# ScanBook.net
KiCad netlist of a schematic drawn in EAGLE
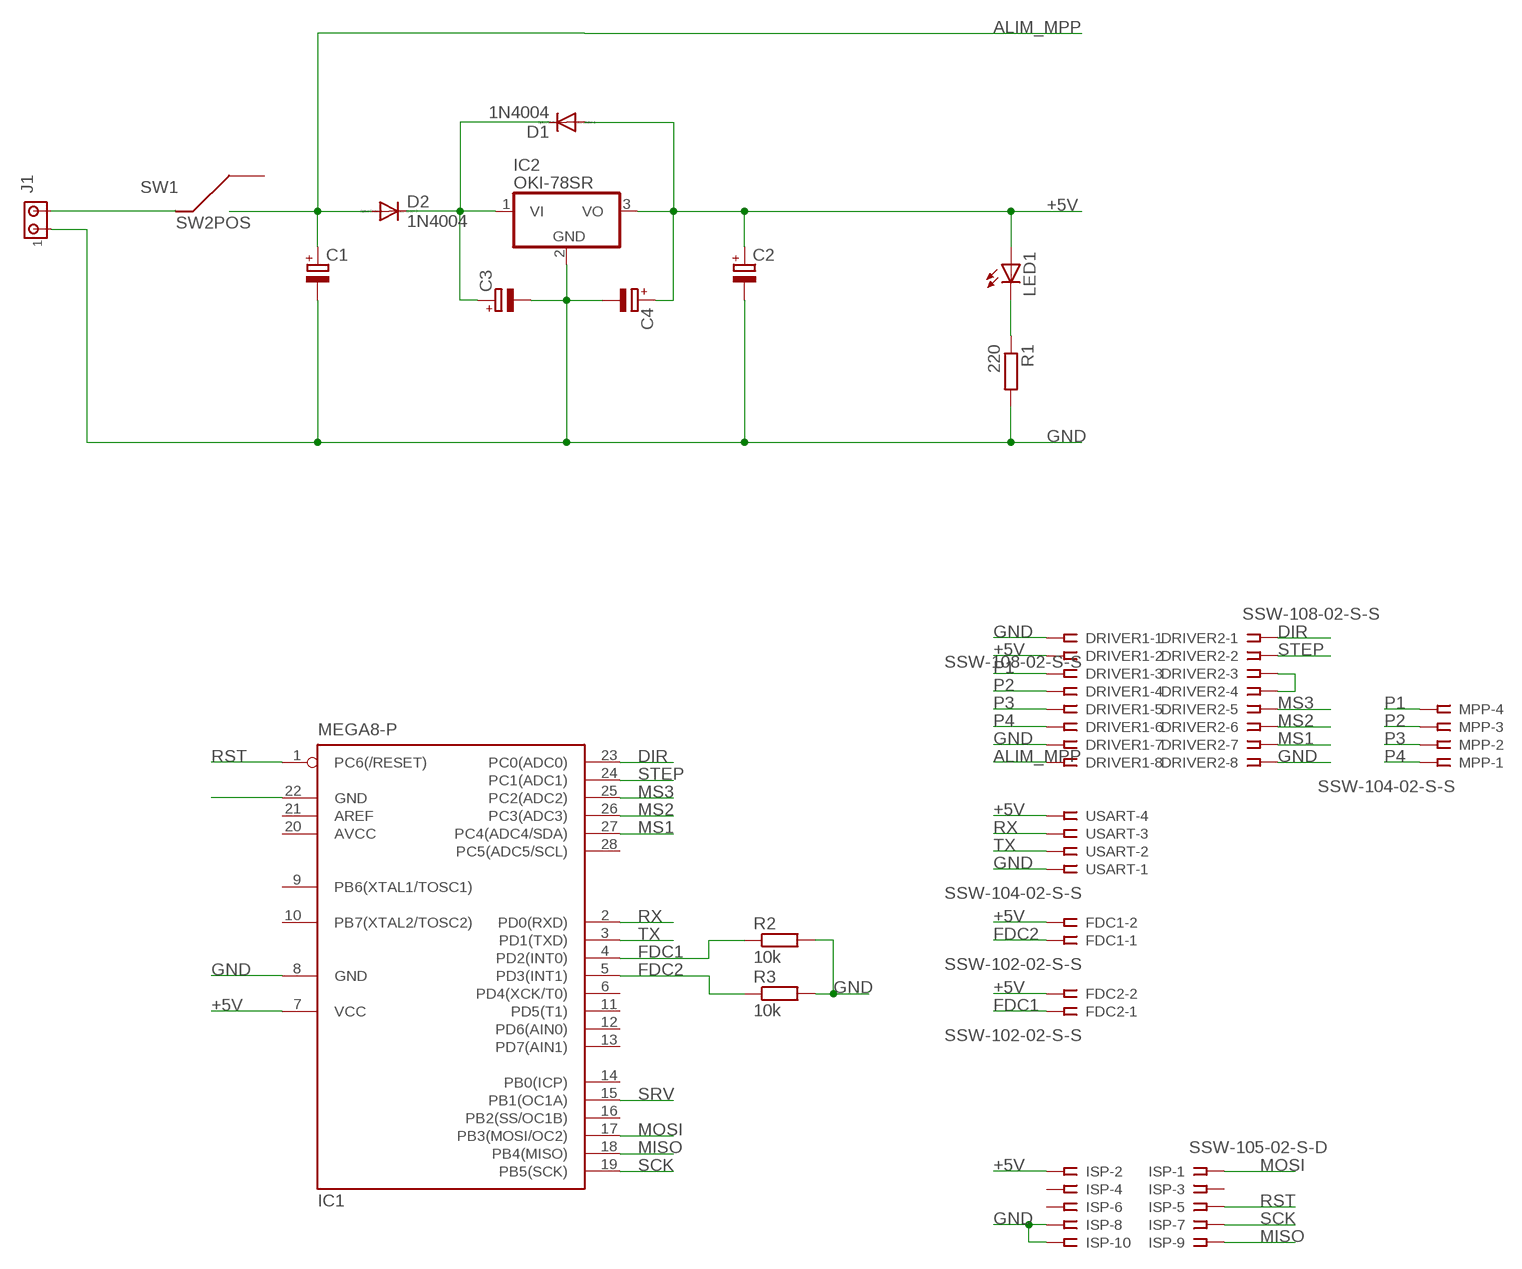
[diagram p0: schematic, sheet 1]

(export (version "E")
  (design (tool "Eeschema 10.0.6"))
  (components
    (comp (ref "C1")
      (value "CPOL-EUE22-9AXIAL")
      (footprint "eagle-import:E22-9")
      (libsource (lib "eagle-import") (part "CPOL-EUE22-9AXIAL"))
    )
    (comp (ref "C2")
      (value "CPOL-EUE22-9AXIAL")
      (footprint "eagle-import:E22-9")
      (libsource (lib "eagle-import") (part "CPOL-EUE22-9AXIAL"))
    )
    (comp (ref "C3")
      (value "CPOL-EUTT2D4")
      (footprint "eagle-import:TT2D4")
      (libsource (lib "eagle-import") (part "CPOL-EUTT2D4"))
    )
    (comp (ref "C4")
      (value "CPOL-EUTT2D4")
      (footprint "eagle-import:TT2D4")
      (libsource (lib "eagle-import") (part "CPOL-EUTT2D4"))
    )
    (comp (ref "D1")
      (value "1N4004")
      (footprint "eagle-import:DO41-10")
      (libsource (lib "eagle-import") (part "1N4004"))
    )
    (comp (ref "D2")
      (value "1N4004")
      (footprint "eagle-import:DO41-10")
      (libsource (lib "eagle-import") (part "1N4004"))
    )
    (comp (ref "DRIVER1")
      (value "SSW-108-02-S-S")
      (footprint "eagle-import:SSW-108-02-S-S")
      (libsource (lib "eagle-import") (part "SSW-108-02-S-S"))
    )
    (comp (ref "DRIVER2")
      (value "SSW-108-02-S-S")
      (footprint "eagle-import:SSW-108-02-S-S")
      (libsource (lib "eagle-import") (part "SSW-108-02-S-S"))
    )
    (comp (ref "FDC1")
      (value "SSW-102-02-S-S")
      (footprint "eagle-import:SSW-102-02-S-S")
      (libsource (lib "eagle-import") (part "SSW-102-02-S-S"))
    )
    (comp (ref "FDC2")
      (value "SSW-102-02-S-S")
      (footprint "eagle-import:SSW-102-02-S-S")
      (libsource (lib "eagle-import") (part "SSW-102-02-S-S"))
    )
    (comp (ref "IC1")
      (value "MEGA8-P")
      (footprint "eagle-import:DIL28-3")
      (libsource (lib "eagle-import") (part "MEGA8-P"))
    )
    (comp (ref "IC2")
      (value "OKI-78SR")
      (footprint "eagle-import:TO220V")
      (libsource (lib "eagle-import") (part "78TV05"))
    )
    (comp (ref "ISP")
      (value "SSW-105-02-S-D")
      (footprint "eagle-import:SSW-105-02-S-D")
      (libsource (lib "eagle-import") (part "SSW-105-02-S-D"))
    )
    (comp (ref "J1")
      (value "MTA02-156")
      (footprint "eagle-import:1X2MTA")
      (libsource (lib "eagle-import") (part "MTA02-156"))
    )
    (comp (ref "LED1")
      (value "LED3MM")
      (footprint "eagle-import:LED3MM")
      (libsource (lib "eagle-import") (part "LED3MM"))
    )
    (comp (ref "MPP")
      (value "SSW-104-02-S-S")
      (footprint "eagle-import:SSW-104-02-S-S")
      (libsource (lib "eagle-import") (part "SSW-104-02-S-S"))
    )
    (comp (ref "R1")
      (value "220")
      (footprint "eagle-import:0207_10")
      (libsource (lib "eagle-import") (part "R-EU_0207/10"))
    )
    (comp (ref "R2")
      (value "10k")
      (footprint "eagle-import:0207_10")
      (libsource (lib "eagle-import") (part "R-EU_0207/10"))
    )
    (comp (ref "R3")
      (value "10k")
      (footprint "eagle-import:0207_10")
      (libsource (lib "eagle-import") (part "R-EU_0207/10"))
    )
    (comp (ref "SW1")
      (value "SW2POS")
      (footprint "eagle-import:SW2POS")
      (libsource (lib "eagle-import") (part "SW2POS"))
    )
    (comp (ref "USART")
      (value "SSW-104-02-S-S")
      (footprint "eagle-import:SSW-104-02-S-S")
      (libsource (lib "eagle-import") (part "SSW-104-02-S-S"))
    )
  )
  (nets
    (net (code "1") (name "/+5V") (class "Default")
      (node (ref "C2") (pin "+") (pinfunction "+_+") (pintype "passive"))
      (node (ref "C4") (pin "+") (pinfunction "+_+") (pintype "passive"))
      (node (ref "D1") (pin "A") (pinfunction "A_A") (pintype "passive"))
      (node (ref "DRIVER1") (pin "2") (pinfunction "1_2") (pintype "passive"))
      (node (ref "FDC1") (pin "2") (pinfunction "1_2") (pintype "passive"))
      (node (ref "FDC2") (pin "2") (pinfunction "1_2") (pintype "passive"))
      (node (ref "IC1") (pin "7") (pinfunction "VCC_7") (pintype "power_in"))
      (node (ref "IC2") (pin "3") (pinfunction "VO_3") (pintype "passive"))
      (node (ref "ISP") (pin "2") (pinfunction "1_2") (pintype "passive"))
      (node (ref "LED1") (pin "A") (pinfunction "A_A") (pintype "passive"))
      (node (ref "USART") (pin "4") (pinfunction "1_4") (pintype "passive"))
    )
    (net (code "2") (name "/ALIM_MPP") (class "Default")
      (node (ref "C1") (pin "+") (pinfunction "+_+") (pintype "passive"))
      (node (ref "D2") (pin "A") (pinfunction "A_A") (pintype "passive"))
      (node (ref "DRIVER1") (pin "8") (pinfunction "1_8") (pintype "passive"))
      (node (ref "SW1") (pin "3") (pinfunction "3_3") (pintype "passive"))
    )
    (net (code "3") (name "/AVCC") (class "Default")
      (node (ref "IC1") (pin "20") (pinfunction "AVCC_20") (pintype "power_in"))
    )
    (net (code "4") (name "/DIR") (class "Default")
      (node (ref "DRIVER2") (pin "1") (pinfunction "1_1") (pintype "passive"))
      (node (ref "IC1") (pin "23") (pinfunction "PC0(ADC0)_23") (pintype "bidirectional"))
    )
    (net (code "5") (name "/FDC1") (class "Default")
      (node (ref "FDC2") (pin "1") (pinfunction "1_1") (pintype "passive"))
      (node (ref "IC1") (pin "4") (pinfunction "PD2(INT0)_4") (pintype "bidirectional"))
      (node (ref "R2") (pin "1") (pinfunction "1_1") (pintype "passive"))
    )
    (net (code "6") (name "/FDC2") (class "Default")
      (node (ref "FDC1") (pin "1") (pinfunction "1_1") (pintype "passive"))
      (node (ref "IC1") (pin "5") (pinfunction "PD3(INT1)_5") (pintype "bidirectional"))
      (node (ref "R3") (pin "1") (pinfunction "1_1") (pintype "passive"))
    )
    (net (code "7") (name "/GND") (class "Default")
      (node (ref "C1") (pin "-") (pinfunction "-_-") (pintype "passive"))
      (node (ref "C2") (pin "-") (pinfunction "-_-") (pintype "passive"))
      (node (ref "C3") (pin "-") (pinfunction "-_-") (pintype "passive"))
      (node (ref "C4") (pin "-") (pinfunction "-_-") (pintype "passive"))
      (node (ref "DRIVER1") (pin "1") (pinfunction "1_1") (pintype "passive"))
      (node (ref "DRIVER1") (pin "7") (pinfunction "1_7") (pintype "passive"))
      (node (ref "DRIVER2") (pin "8") (pinfunction "1_8") (pintype "passive"))
      (node (ref "IC1") (pin "8") (pinfunction "GND_8") (pintype "power_in"))
      (node (ref "IC2") (pin "2") (pinfunction "GND_2") (pintype "passive"))
      (node (ref "ISP") (pin "10") (pinfunction "1_10") (pintype "passive"))
      (node (ref "ISP") (pin "8") (pinfunction "1_8") (pintype "passive"))
      (node (ref "J1") (pin "1") (pinfunction "1_1") (pintype "passive"))
      (node (ref "R1") (pin "2") (pinfunction "2_2") (pintype "passive"))
      (node (ref "R2") (pin "2") (pinfunction "2_2") (pintype "passive"))
      (node (ref "R3") (pin "2") (pinfunction "2_2") (pintype "passive"))
      (node (ref "USART") (pin "1") (pinfunction "1_1") (pintype "passive"))
    )
    (net (code "8") (name "/MISO") (class "Default")
      (node (ref "IC1") (pin "18") (pinfunction "PB4(MISO)_18") (pintype "bidirectional"))
      (node (ref "ISP") (pin "9") (pinfunction "1_9") (pintype "passive"))
    )
    (net (code "9") (name "/MOSI") (class "Default")
      (node (ref "IC1") (pin "17") (pinfunction "PB3(MOSI/OC2)_17") (pintype "bidirectional"))
      (node (ref "ISP") (pin "1") (pinfunction "1_1") (pintype "passive"))
    )
    (net (code "10") (name "/MS1") (class "Default")
      (node (ref "DRIVER2") (pin "7") (pinfunction "1_7") (pintype "passive"))
      (node (ref "IC1") (pin "27") (pinfunction "PC4(ADC4/SDA)_27") (pintype "bidirectional"))
    )
    (net (code "11") (name "/MS2") (class "Default")
      (node (ref "DRIVER2") (pin "6") (pinfunction "1_6") (pintype "passive"))
      (node (ref "IC1") (pin "26") (pinfunction "PC3(ADC3)_26") (pintype "bidirectional"))
    )
    (net (code "12") (name "/MS3") (class "Default")
      (node (ref "DRIVER2") (pin "5") (pinfunction "1_5") (pintype "passive"))
      (node (ref "IC1") (pin "25") (pinfunction "PC2(ADC2)_25") (pintype "bidirectional"))
    )
    (net (code "13") (name "/P1") (class "Default")
      (node (ref "DRIVER1") (pin "3") (pinfunction "1_3") (pintype "passive"))
      (node (ref "MPP") (pin "4") (pinfunction "1_4") (pintype "passive"))
    )
    (net (code "14") (name "/P2") (class "Default")
      (node (ref "DRIVER1") (pin "4") (pinfunction "1_4") (pintype "passive"))
      (node (ref "MPP") (pin "3") (pinfunction "1_3") (pintype "passive"))
    )
    (net (code "15") (name "/P3") (class "Default")
      (node (ref "DRIVER1") (pin "5") (pinfunction "1_5") (pintype "passive"))
      (node (ref "MPP") (pin "2") (pinfunction "1_2") (pintype "passive"))
    )
    (net (code "16") (name "/P4") (class "Default")
      (node (ref "DRIVER1") (pin "6") (pinfunction "1_6") (pintype "passive"))
      (node (ref "MPP") (pin "1") (pinfunction "1_1") (pintype "passive"))
    )
    (net (code "17") (name "/RST") (class "Default")
      (node (ref "IC1") (pin "1") (pinfunction "PC6(/RESET)_1") (pintype "bidirectional"))
      (node (ref "ISP") (pin "5") (pinfunction "1_5") (pintype "passive"))
    )
    (net (code "18") (name "/RX") (class "Default")
      (node (ref "IC1") (pin "2") (pinfunction "PD0(RXD)_2") (pintype "bidirectional"))
      (node (ref "USART") (pin "3") (pinfunction "1_3") (pintype "passive"))
    )
    (net (code "19") (name "/SCK") (class "Default")
      (node (ref "IC1") (pin "19") (pinfunction "PB5(SCK)_19") (pintype "bidirectional"))
      (node (ref "ISP") (pin "7") (pinfunction "1_7") (pintype "passive"))
    )
    (net (code "20") (name "/SRV") (class "Default")
      (node (ref "IC1") (pin "15") (pinfunction "PB1(OC1A)_15") (pintype "bidirectional"))
    )
    (net (code "21") (name "/STEP") (class "Default")
      (node (ref "DRIVER2") (pin "2") (pinfunction "1_2") (pintype "passive"))
      (node (ref "IC1") (pin "24") (pinfunction "PC1(ADC1)_24") (pintype "bidirectional"))
    )
    (net (code "22") (name "/TX") (class "Default")
      (node (ref "IC1") (pin "3") (pinfunction "PD1(TXD)_3") (pintype "bidirectional"))
      (node (ref "USART") (pin "2") (pinfunction "1_2") (pintype "passive"))
    )
    (net (code "23") (name "Net-(DRIVER2C-1)") (class "Default")
      (node (ref "DRIVER2") (pin "3") (pinfunction "1_3") (pintype "passive"))
      (node (ref "DRIVER2") (pin "4") (pinfunction "1_4") (pintype "passive"))
    )
    (net (code "24") (name "Net-(IC2-VI)") (class "Default")
      (node (ref "C3") (pin "+") (pinfunction "+_+") (pintype "passive"))
      (node (ref "D1") (pin "C") (pinfunction "C_C") (pintype "passive"))
      (node (ref "D2") (pin "C") (pinfunction "C_C") (pintype "passive"))
      (node (ref "IC2") (pin "1") (pinfunction "VI_1") (pintype "input"))
    )
    (net (code "25") (name "Net-(J1-Pad2)") (class "Default")
      (node (ref "J1") (pin "2") (pinfunction "2_2") (pintype "passive"))
      (node (ref "SW1") (pin "2") (pinfunction "2_2") (pintype "passive"))
    )
    (net (code "26") (name "Net-(LED1-C)") (class "Default")
      (node (ref "LED1") (pin "K") (pinfunction "C_K") (pintype "passive"))
      (node (ref "R1") (pin "1") (pinfunction "1_1") (pintype "passive"))
    )
    (net (code "27") (name "unconnected-(IC1-AREF-Pad21)") (class "Default")
      (node (ref "IC1") (pin "21") (pinfunction "AREF_21") (pintype "passive"))
    )
    (net (code "28") (name "unconnected-(IC1-GND-Pad22)") (class "Default")
      (node (ref "IC1") (pin "22") (pinfunction "GND_22") (pintype "power_in"))
    )
    (net (code "29") (name "unconnected-(IC1-PB0(ICP)-Pad14)") (class "Default")
      (node (ref "IC1") (pin "14") (pinfunction "PB0(ICP)_14") (pintype "bidirectional"))
    )
    (net (code "30") (name "unconnected-(IC1-PB2(SS{slash}OC1B)-Pad16)") (class "Default")
      (node (ref "IC1") (pin "16") (pinfunction "PB2(SS/OC1B)_16") (pintype "bidirectional"))
    )
    (net (code "31") (name "unconnected-(IC1-PB6(XTAL1{slash}TOSC1)-Pad9)") (class "Default")
      (node (ref "IC1") (pin "9") (pinfunction "PB6(XTAL1/TOSC1)_9") (pintype "bidirectional"))
    )
    (net (code "32") (name "unconnected-(IC1-PB7(XTAL2{slash}TOSC2)-Pad10)") (class "Default")
      (node (ref "IC1") (pin "10") (pinfunction "PB7(XTAL2/TOSC2)_10") (pintype "bidirectional"))
    )
    (net (code "33") (name "unconnected-(IC1-PC5(ADC5{slash}SCL)-Pad28)") (class "Default")
      (node (ref "IC1") (pin "28") (pinfunction "PC5(ADC5/SCL)_28") (pintype "bidirectional"))
    )
    (net (code "34") (name "unconnected-(IC1-PD4(XCK{slash}T0)-Pad6)") (class "Default")
      (node (ref "IC1") (pin "6") (pinfunction "PD4(XCK/T0)_6") (pintype "bidirectional"))
    )
    (net (code "35") (name "unconnected-(IC1-PD5(T1)-Pad11)") (class "Default")
      (node (ref "IC1") (pin "11") (pinfunction "PD5(T1)_11") (pintype "bidirectional"))
    )
    (net (code "36") (name "unconnected-(IC1-PD6(AIN0)-Pad12)") (class "Default")
      (node (ref "IC1") (pin "12") (pinfunction "PD6(AIN0)_12") (pintype "bidirectional"))
    )
    (net (code "37") (name "unconnected-(IC1-PD7(AIN1)-Pad13)") (class "Default")
      (node (ref "IC1") (pin "13") (pinfunction "PD7(AIN1)_13") (pintype "bidirectional"))
    )
    (net (code "38") (name "unconnected-(ISPD-1-Pad3)") (class "Default")
      (node (ref "ISP") (pin "3") (pinfunction "1_3") (pintype "passive"))
    )
    (net (code "39") (name "unconnected-(ISPE-1-Pad4)") (class "Default")
      (node (ref "ISP") (pin "4") (pinfunction "1_4") (pintype "passive"))
    )
    (net (code "40") (name "unconnected-(ISPG-1-Pad6)") (class "Default")
      (node (ref "ISP") (pin "6") (pinfunction "1_6") (pintype "passive"))
    )
    (net (code "41") (name "unconnected-(SW1-Pad1)") (class "Default")
      (node (ref "SW1") (pin "1") (pinfunction "1_1") (pintype "passive"))
    )
  )
)
